# Interface_-_RS485.net
KiCad netlist of a schematic drawn in Altium Designer
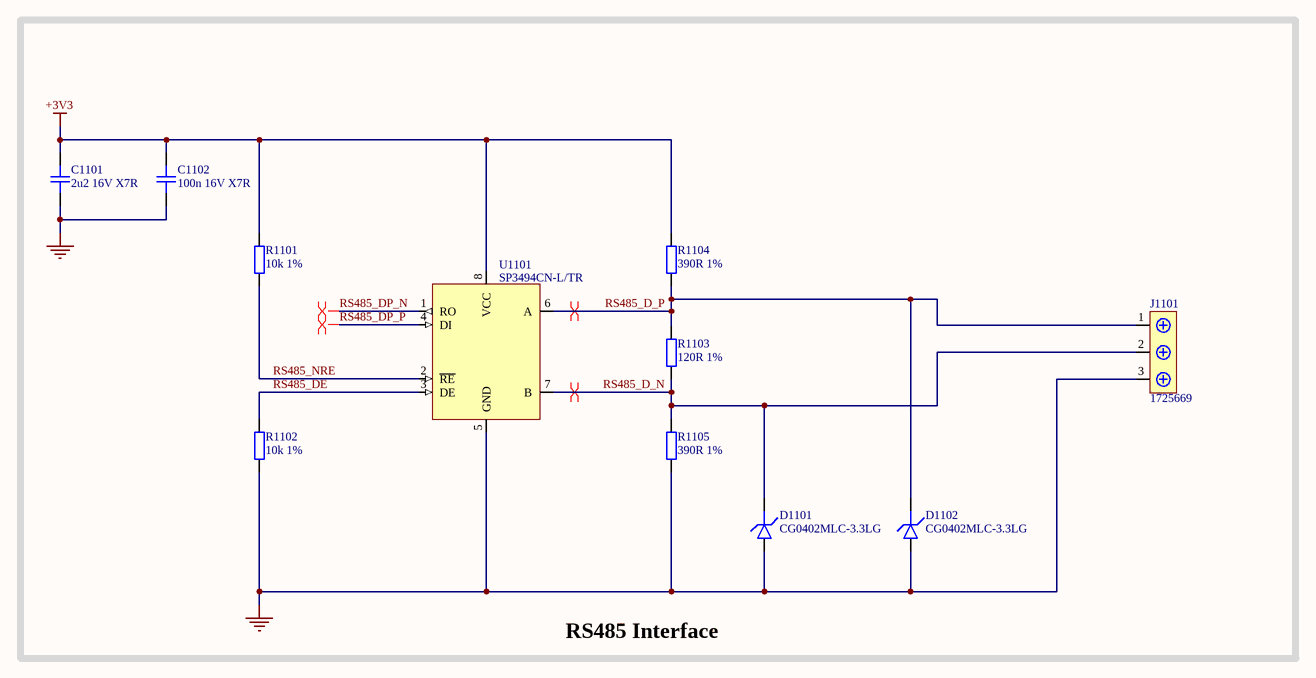
[diagram p0: Interface - RS485.SchDoc]

(export (version "E")
  (design (tool "Eeschema 10.0.6"))
  (components
    (comp (ref "C1101")
      (value "2u2 16V X7R")
      (footprint "CAP_0603")
      (description "Capacitor SMD 0603")
      (fields
        (field (name "MANUFACTURER") "YAGEO")
        (field (name "MANUFACTURER PART NUMBER") "CC0603KRX7R7BB225")
      )
      (libsource (lib "Schematic-Lib-PhilsLab") (part "CAP_0603"))
    )
    (comp (ref "C1102")
      (value "100n 16V X7R")
      (footprint "CAP_0402")
      (description "Capacitor SMD 0402")
      (fields
        (field (name "MANUFACTURER") "YAGEO")
        (field (name "MANUFACTURER PART NUMBER") "CC0402JRX7R7BB104")
      )
      (libsource (lib "Schematic-Lib-PhilsLab") (part "CAP_0402"))
    )
    (comp (ref "D1101")
      (value "CG0402MLC-3.3LG")
      (footprint "D_0402")
      (description "Diode TVS / ESD 0402")
      (libsource (lib "Schematic-Lib-PhilsLab") (part "D_TVS_0402"))
    )
    (comp (ref "D1102")
      (value "CG0402MLC-3.3LG")
      (footprint "D_0402")
      (description "Diode TVS / ESD 0402")
      (libsource (lib "Schematic-Lib-PhilsLab") (part "D_TVS_0402"))
    )
    (comp (ref "J1101")
      (value "1725669")
      (footprint "1725669")
      (description "Screw Terminal Block 3 Positions 2.54mm")
      (fields (field (name "MANUFACTURER") "Phoenix"))
      (libsource (lib "Schematic-Lib") (part "1725669"))
    )
    (comp (ref "R1101")
      (value "10k 1%")
      (footprint "RES_0402")
      (description "Resistor SMD 0402")
      (fields
        (field (name "MANUFACTURER") "PANASONIC")
        (field (name "MANUFACTURER PART NUMBER") "ERJPA2F1002X")
      )
      (libsource (lib "Schematic-Lib-PhilsLab") (part "RES_0402"))
    )
    (comp (ref "R1102")
      (value "10k 1%")
      (footprint "RES_0402")
      (description "Resistor SMD 0402")
      (fields
        (field (name "MANUFACTURER") "PANASONIC")
        (field (name "MANUFACTURER PART NUMBER") "ERJPA2F1002X")
      )
      (libsource (lib "Schematic-Lib-PhilsLab") (part "RES_0402"))
    )
    (comp (ref "R1103")
      (value "120R 1%")
      (footprint "RES_0402")
      (description "Resistor SMD 0402")
      (fields
        (field (name "MANUFACTURER") "PANASONIC")
        (field (name "MANUFACTURER PART NUMBER") "ERJ2GEJ121X")
      )
      (libsource (lib "Schematic-Lib-PhilsLab") (part "RES_0402"))
    )
    (comp (ref "R1104")
      (value "390R 1%")
      (footprint "RES_0402")
      (description "Resistor SMD 0402")
      (fields
        (field (name "MANUFACTURER") "PANASONIC")
        (field (name "MANUFACTURER PART NUMBER") "ERJ2GEJ391X")
      )
      (libsource (lib "Schematic-Lib-PhilsLab") (part "RES_0402"))
    )
    (comp (ref "R1105")
      (value "390R 1%")
      (footprint "RES_0402")
      (description "Resistor SMD 0402")
      (fields
        (field (name "MANUFACTURER") "PANASONIC")
        (field (name "MANUFACTURER PART NUMBER") "ERJ2GEJ391X")
      )
      (libsource (lib "Schematic-Lib-PhilsLab") (part "RES_0402"))
    )
    (comp (ref "U1101")
      (value "SP3494CN-L/TR")
      (footprint "SOIC-8")
      (description "3.3V Low Power RS-485 / RS-422 Transceiver SOIC-8")
      (fields (field (name "MANUFACTURER") "MaxLinear"))
      (libsource (lib "Schematic-Lib-PhilsLab") (part "SP3494CN-L/TR"))
    )
  )
  (nets
    (net (code "1") (name "+3V3") (class "Default")
      (node (ref "C1101") (pin "2") (pinfunction "2_2") (pintype "passive"))
      (node (ref "C1102") (pin "2") (pinfunction "2_2") (pintype "passive"))
      (node (ref "R1101") (pin "2") (pinfunction "2_2") (pintype "passive"))
      (node (ref "R1104") (pin "2") (pinfunction "2_2") (pintype "passive"))
      (node (ref "U1101") (pin "8") (pinfunction "VCC_8") (pintype "power_in"))
    )
    (net (code "2") (name "/RS485_DE") (class "Default")
      (node (ref "R1102") (pin "2") (pinfunction "2_2") (pintype "passive"))
      (node (ref "U1101") (pin "3") (pinfunction "DE_3") (pintype "input"))
    )
    (net (code "3") (name "/RS485_DP_N") (class "Default")
      (node (ref "U1101") (pin "1") (pinfunction "RO_1") (pintype "output"))
    )
    (net (code "4") (name "/RS485_DP_P") (class "Default")
      (node (ref "U1101") (pin "4") (pinfunction "DI_4") (pintype "input"))
    )
    (net (code "5") (name "/RS485_D_N") (class "Default")
      (node (ref "D1101") (pin "K") (pinfunction "K_K") (pintype "passive"))
      (node (ref "J1101") (pin "2") (pinfunction "2_2") (pintype "passive"))
      (node (ref "R1103") (pin "1") (pinfunction "1_1") (pintype "passive"))
      (node (ref "R1105") (pin "2") (pinfunction "2_2") (pintype "passive"))
      (node (ref "U1101") (pin "7") (pinfunction "B_7") (pintype "bidirectional"))
    )
    (net (code "6") (name "/RS485_D_P") (class "Default")
      (node (ref "D1102") (pin "K") (pinfunction "K_K") (pintype "passive"))
      (node (ref "J1101") (pin "1") (pinfunction "1_1") (pintype "passive"))
      (node (ref "R1103") (pin "2") (pinfunction "2_2") (pintype "passive"))
      (node (ref "R1104") (pin "1") (pinfunction "1_1") (pintype "passive"))
      (node (ref "U1101") (pin "6") (pinfunction "A_6") (pintype "bidirectional"))
    )
    (net (code "7") (name "/RS485_NRE") (class "Default")
      (node (ref "R1101") (pin "1") (pinfunction "1_1") (pintype "passive"))
      (node (ref "U1101") (pin "2") (pinfunction "~{RE}_2") (pintype "input"))
    )
    (net (code "8") (name "GND") (class "Default")
      (node (ref "C1101") (pin "1") (pinfunction "1_1") (pintype "passive"))
      (node (ref "C1102") (pin "1") (pinfunction "1_1") (pintype "passive"))
      (node (ref "D1101") (pin "A") (pinfunction "A_A") (pintype "passive"))
      (node (ref "D1102") (pin "A") (pinfunction "A_A") (pintype "passive"))
      (node (ref "J1101") (pin "3") (pinfunction "3_3") (pintype "passive"))
      (node (ref "R1102") (pin "1") (pinfunction "1_1") (pintype "passive"))
      (node (ref "R1105") (pin "1") (pinfunction "1_1") (pintype "passive"))
      (node (ref "U1101") (pin "5") (pinfunction "GND_5") (pintype "power_in"))
    )
  )
)
